# AQM_with_esp32.net
KiCad netlist of a schematic drawn in Altium Designer
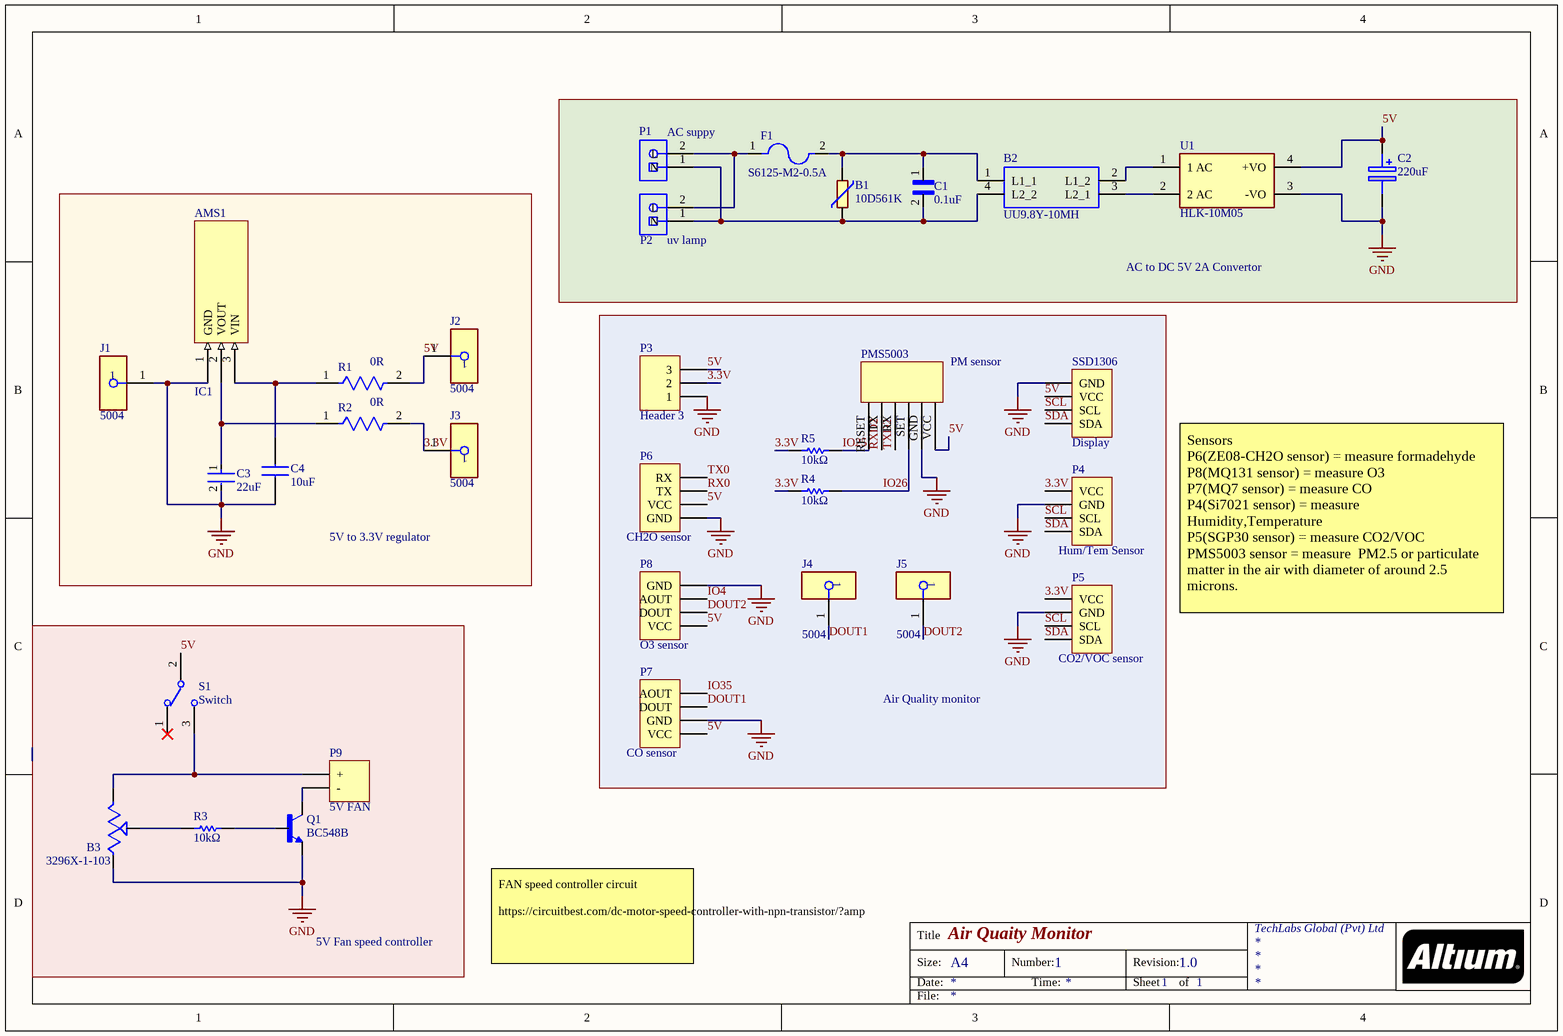
[diagram p0: AQM with esp32.SchDoc]

(export (version "E")
  (design (tool "Eeschema 10.0.6"))
  (components
    (comp (ref "AMS1")
      (value "IC1")
      (footprint "SOT89-150P350X150-3N")
      (fields
        (field (name "MANUFACTURER") "YONGYUTAI")
        (field (name "MFR. PART #") "AMS1117-3.3")
        (field (name "LCSC PART #") "C2904742")
      )
      (libsource (lib "AMS1117-3.3") (part "IC?"))
    )
    (comp (ref "B1")
      (value "10D561K")
      (footprint "10D561K")
      (description "920V 42.3J 180pF@1kHz 460V 350V 504V~616V 2.5kA Plugin Varistors ROHS")
      (fields (field (name "LCSC PART #") "C113236") (field (name "MANUFACTURER") "Hongzhi Elec"))
      (libsource (lib "10D561K") (part "10D561K"))
    )
    (comp (ref "B2")
      (value "UU9.8Y-10MH")
      (footprint "UU98Y10MH")
      (description "10mH@1kHz 1.2Ω 2 500mA 50V Plugin Common Mode Filters ROHS")
      (fields
        (field (name "MANUFACTURER") "FH (Guangdong Fenghua Advanced Tech)")
        (field (name "LCSC PART#") "C75192")
      )
      (libsource (lib "UU9.8Y-10MH") (part "UU9.8Y-10MH"))
    )
    (comp (ref "B3")
      (value "3296X-1-103")
      (footprint "3296X1223LF")
      (description "±10% 10kΩ Plugin Variable Resistors/Potentiometers ROHS")
      (fields
        (field (name "LCSC PART #") "C118955")
        (field (name "MANUFACTURER") "BOCHEN(Chengdu Guosheng Tech)")
      )
      (libsource (lib "3296X-1-103") (part "3296X-1-103"))
    )
    (comp (ref "C1")
      (value "0.1uF")
      (footprint "MPX-104K275VAC-C-D2")
      (description "0.1uF ±10% -40℃~+110℃ X2 275VAC Radial Leaded,P=15mm Suppression Capacitors ROHS")
      (fields (field (name "LCSC PART #") "C3249976") (field (name "MANUFACTURER") "CORETONG"))
      (libsource (lib "MPX-104K275VAC-C-D2") (part "MPX-104K275VAC-C-D2"))
    )
    (comp (ref "C2")
      (value "220uF")
      (footprint "CAPAE830X1050N")
      (fields
        (field (name "MANUFACTURER") "Nichicon")
        (field (name "MFR.PART #") "UUR1C221MNL1GS")
        (field (name "LCSC PART#") "C445237")
      )
      (libsource (lib "UUR1C221MNL1GS") (part "UUR1C221MNL1GS"))
    )
    (comp (ref "C3")
      (value "22uF")
      (footprint "FP-GRM219-0_2-0_15-IPC_A")
      (description "Chip Multilayer Ceramic Capacitors for General Purpose, 0805, 22uF, X5R, 15%, 20%, 16V")
      (fields (field (name "MFR. PART #") "GRM219R61C226ME15L") (field (name "LCSC PART #") "C162295"))
      (libsource (lib "Altium Content Vault") (part "b4654b650e69147ec39a6b967a45e02"))
    )
    (comp (ref "C4")
      (value "10uF")
      (footprint "CAPC1005X70N")
      (description "6.3V 10uF X5R ±20% 0402 Multilayer Ceramic Capacitors MLCC - SMD/SMT ROHS")
      (fields
        (field (name "MANUFACTURER") "Samsung Electro-Mechanics")
        (field (name "MFR. PART #") "CL05A106MQ5NUNC")
      )
      (libsource (lib "CL05A106MQ5NUNC") (part "CL05A106MQ5NUNC"))
    )
    (comp (ref "F1")
      (value "S6125-M2-0.5A")
      (footprint "CAPC6125X25N")
      (description "SMD Fuses ROHS")
      (fields (field (name "LCSC PART #") "C845172") (field (name "MANUFACTURER") "SART(Nanjing Sart Tech)"))
      (libsource (lib "S6125-M2-0.5A") (part "S6125-M2-0.5A"))
    )
    (comp (ref "J1")
      (value "5004")
      (footprint "FP-5004-MFG")
      (description "PC TEST POINT MINIATURE YELLOW")
      (fields (field (name "MANUFACTURER") "Keystone") (field (name "LCSC PART #") "C2906762"))
      (libsource (lib "") (part "98815daf2f2c152b0c43f5ab9800df6_2"))
    )
    (comp (ref "J2")
      (value "5004")
      (footprint "FP-5004-MFG")
      (description "PC TEST POINT MINIATURE YELLOW")
      (fields (field (name "MANUFACTURER") "Keystone") (field (name "LCSC PART #") "C2906762"))
      (libsource (lib "Altium Content Vault") (part "98815daf2f2c152b0c43f5ab9800df6"))
    )
    (comp (ref "J3")
      (value "5004")
      (footprint "FP-5004-MFG")
      (description "PC TEST POINT MINIATURE YELLOW")
      (fields (field (name "MANUFACTURER") "Keystone") (field (name "LCSC PART #") "C2906762"))
      (libsource (lib "Altium Content Vault") (part "98815daf2f2c152b0c43f5ab9800df6"))
    )
    (comp (ref "J4")
      (value "5004")
      (footprint "FP-5004-MFG")
      (description "PC TEST POINT MINIATURE YELLOW")
      (fields (field (name "MANUFACTURER") "Keystone") (field (name "LCSC PART #") "C2906762"))
      (libsource (lib "") (part "98815daf2f2c152b0c43f5ab9800df6_1"))
    )
    (comp (ref "J5")
      (value "5004")
      (footprint "FP-5004-MFG")
      (description "PC TEST POINT MINIATURE YELLOW")
      (fields (field (name "MANUFACTURER") "Keystone") (field (name "LCSC PART #") "C2906762"))
      (libsource (lib "") (part "98815daf2f2c152b0c43f5ab9800df6_1"))
    )
    (comp (ref "P1")
      (value "AC suppy")
      (footprint "PHOE-1729128-2_V")
      (description "13.5A 400V Green Straight pin 5.08mm 1 2 Plugin,P=5.08mm Screw terminal ROHS")
      (fields (field (name "MFR.PART #") "1729128") (field (name "LCSC PART#") "C91153"))
      (libsource (lib "Altium Content Vault") (part "CN-2P-F-R2"))
    )
    (comp (ref "P2")
      (value "uv lamp")
      (footprint "PHOE-1729128-2_V")
      (description "13.5A 400V Green Straight pin 5.08mm 1 2 Plugin,P=5.08mm Screw terminal ROHS")
      (fields (field (name "MFR.PART #") "1729128") (field (name "LCSC PART#") "C91153"))
      (libsource (lib "Altium Content Vault") (part "CN-2P-F-R2"))
    )
    (comp (ref "P3")
      (value "Header 3")
      (footprint "HDR1X3")
      (description "Header, 3-Pin")
      (fields (field (name "PUBLISHER") "Altium Limited"))
      (libsource (lib "Miscellaneous Connectors") (part "Header 3"))
    )
    (comp (ref "P4")
      (value "Hum/Tem Sensor")
      (footprint "HDR1X4")
      (description "Si7021 Header, 4-Pin")
      (libsource (lib "") (part "Header 4_2"))
    )
    (comp (ref "P5")
      (value "CO2/VOC sensor")
      (footprint "HDR1X4")
      (description "SGP30 Header, 4-Pin")
      (fields (field (name "PUBLISHER") "Altium Limited"))
      (libsource (lib "") (part "Header 4_2"))
    )
    (comp (ref "P6")
      (value "CH2O sensor")
      (footprint "HDR1X4")
      (description "- Sensor Modules ROHS")
      (fields
        (field (name "MFR.PART #") "ZE08-CH2O")
        (field (name "MANUFACTURER") "Zhengzhou Winsen Elec Tech")
      )
      (libsource (lib "") (part "Header 4_3"))
    )
    (comp (ref "P7")
      (value "CO sensor")
      (footprint "HDR1X4")
      (description "MQ7 Header, 4-Pin")
      (fields (field (name "PUBLISHER") "Altium Limited"))
      (libsource (lib "Miscellaneous Connectors") (part "Header 4"))
    )
    (comp (ref "P8")
      (value "O3 sensor")
      (footprint "HDR1X4")
      (description "MQ131 Header, 4-Pin")
      (fields (field (name "PUBLISHER") "Altium Limited"))
      (libsource (lib "") (part "Header 4_1"))
    )
    (comp (ref "P9")
      (value "5V FAN")
      (footprint "HDR1X2")
      (description "Header, 2-Pin")
      (fields (field (name "PUBLISHER") "Altium Limited"))
      (libsource (lib "Miscellaneous Connectors") (part "Header 2"))
    )
    (comp (ref "PMS5003")
      (value "PM sensor")
      (footprint "PMS5003 PM2.5 Sensor")
      (description "PMS5003 Sensor Modules ROHS")
      (fields (field (name "MFR.PART #") "PMS5003") (field (name "MANUFACTURER") "Beijing Plantower"))
      (libsource (lib "DIY Air Quality Monitor Library") (part "PMS5003 PM2.5 Sensor"))
    )
    (comp (ref "Q1")
      (value "BC548B")
      (footprint "BC548B")
      (fields (field (name "MANUFACTURER") "LGE") (field (name "LCSC PART#") "C713615"))
      (libsource (lib "BC548B") (part "BC548B"))
    )
    (comp (ref "R1")
      (value "0R")
      (footprint "FP-RC0402-0_4-IPC_A")
      (description "RES SMD 0 OHM JUMPER 1/16W 0402")
      (fields (field (name "MANUFACTURER") "Yageo") (field (name "LCSC PART #") "C106231"))
      (libsource (lib "Altium Content Vault") (part "1029c3af85768c4190bb7ad29bc67b5"))
    )
    (comp (ref "R2")
      (value "0R")
      (footprint "FP-RC0402-0_4-IPC_A")
      (description "RES SMD 0 OHM JUMPER 1/16W 0402")
      (fields (field (name "MANUFACTURER") "Yageo") (field (name "LCSC PART #") "C106231"))
      (libsource (lib "Altium Content Vault") (part "1029c3af85768c4190bb7ad29bc67b5"))
    )
    (comp (ref "R3")
      (value "10kΩ")
      (footprint "RESC1005X40X25LL05T10")
      (description "62.5mW 50V ±100ppm/℃ ±1% -55℃~+155℃ 10kΩ 0402 Chip Resistor - Surface Mount ROHS")
      (fields (field (name "MFR. PART #") "RC0402FR-0710KL") (field (name "MANUFACTURER") "Yageo / Phycomp"))
      (libsource (lib "Altium Content Vault") (part "RES"))
    )
    (comp (ref "R4")
      (value "10kΩ")
      (footprint "RESC1005X40X25LL05T10")
      (description "62.5mW 50V ±100ppm/℃ ±1% -55℃~+155℃ 10kΩ 0402 Chip Resistor - Surface Mount ROHS")
      (fields (field (name "MFR. PART #") "RC0402FR-0710KL") (field (name "MANUFACTURER") "Yageo / Phycomp"))
      (libsource (lib "Altium Content Vault") (part "RES"))
    )
    (comp (ref "R5")
      (value "10kΩ")
      (footprint "RESC1005X40X25LL05T10")
      (description "62.5mW 50V ±100ppm/℃ ±1% -55℃~+155℃ 10kΩ 0402 Chip Resistor - Surface Mount ROHS")
      (fields (field (name "MFR. PART #") "RC0402FR-0710KL") (field (name "MANUFACTURER") "Yageo / Phycomp"))
      (libsource (lib "Altium Content Vault") (part "RES"))
    )
    (comp (ref "S1")
      (value "Switch")
      (footprint "SK3245SL1A")
      (fields
        (field (name "MANUFACTURER") "XKB Connectivity")
        (field (name "MFR. PART #") "SK-3245S-L1-A")
        (field (name "LCSC PART #") "C405951")
      )
      (libsource (lib "SK-3245S-L1-A") (part "SK-3245S-L1-A"))
    )
    (comp (ref "SSD1306")
      (value "Display")
      (footprint "HDR1X4")
      (description "Header, 4-Pin")
      (fields (field (name "PUBLISHER") "Altium Limited"))
      (libsource (lib "") (part "Header 4_4"))
    )
    (comp (ref "U1")
      (value "HLK-10M05")
      (footprint "FP-HLK-10M05-MFG")
      (description "5V 2A 90VAC~265VAC 1 120V~350V Isolated Regulated 10W AC-DC 80% Plugin Power Modules ROHS")
      (fields (field (name "MANUFACTURER") "HI-LINK") (field (name "LCSC PART#") "C403745"))
      (libsource (lib "Altium Content Vault") (part "a65b17ccb3a75dffb3c3e849074403b"))
    )
  )
  (nets
    (net (code "1") (name "/3.3V") (class "Default")
      (node (ref "J3") (pin "1") (pinfunction "1_1") (pintype "passive"))
      (node (ref "P3") (pin "2") (pinfunction "2_2") (pintype "passive"))
      (node (ref "P4") (pin "1") (pinfunction "VCC_1") (pintype "passive"))
      (node (ref "P5") (pin "1") (pinfunction "VCC_1") (pintype "passive"))
      (node (ref "R2") (pin "2") (pinfunction "2_2") (pintype "passive"))
      (node (ref "R4") (pin "1") (pinfunction "1_1") (pintype "passive"))
      (node (ref "R5") (pin "1") (pinfunction "1_1") (pintype "passive"))
    )
    (net (code "2") (name "/5V") (class "Default")
      (node (ref "C2") (pin "1") (pinfunction "+_1") (pintype "passive"))
      (node (ref "J2") (pin "1") (pinfunction "1_1") (pintype "passive"))
      (node (ref "P3") (pin "3") (pinfunction "3_3") (pintype "passive"))
      (node (ref "P6") (pin "2") (pinfunction "VCC_2") (pintype "passive"))
      (node (ref "P7") (pin "1") (pinfunction "VCC_1") (pintype "passive"))
      (node (ref "P8") (pin "1") (pinfunction "VCC_1") (pintype "passive"))
      (node (ref "PMS5003") (pin "VCC") (pintype "passive"))
      (node (ref "R1") (pin "2") (pinfunction "2_2") (pintype "passive"))
      (node (ref "S1") (pin "2") (pinfunction "2_2") (pintype "passive"))
      (node (ref "SSD1306") (pin "2") (pinfunction "VCC_2") (pintype "passive"))
      (node (ref "U1") (pin "4") (pinfunction "+VO_4") (pintype "power_in"))
    )
    (net (code "3") (name "/DOUT1") (class "Default")
      (node (ref "J4") (pin "1") (pinfunction "1_1") (pintype "passive"))
      (node (ref "P7") (pin "3") (pinfunction "DOUT_3") (pintype "passive"))
    )
    (net (code "4") (name "/DOUT2") (class "Default")
      (node (ref "J5") (pin "1") (pinfunction "1_1") (pintype "passive"))
      (node (ref "P8") (pin "2") (pinfunction "DOUT_2") (pintype "passive"))
    )
    (net (code "5") (name "/IO4") (class "Default")
      (node (ref "P8") (pin "3") (pinfunction "AOUT_3") (pintype "passive"))
    )
    (net (code "6") (name "/IO25") (class "Default")
      (node (ref "PMS5003") (pin "RESET") (pintype "passive"))
      (node (ref "R5") (pin "2") (pinfunction "2_2") (pintype "passive"))
    )
    (net (code "7") (name "/IO26") (class "Default")
      (node (ref "PMS5003") (pin "SET") (pintype "passive"))
      (node (ref "R4") (pin "2") (pinfunction "2_2") (pintype "passive"))
    )
    (net (code "8") (name "/IO35") (class "Default")
      (node (ref "P7") (pin "4") (pinfunction "AOUT_4") (pintype "passive"))
    )
    (net (code "9") (name "/RX0") (class "Default")
      (node (ref "P6") (pin "3") (pinfunction "TX_3") (pintype "passive"))
    )
    (net (code "10") (name "/RXD2") (class "Default") (node (ref "PMS5003") (pin "TX") (pintype "passive")))
    (net (code "11") (name "/SCL") (class "Default")
      (node (ref "P4") (pin "3") (pinfunction "SCL_3") (pintype "passive"))
      (node (ref "P5") (pin "3") (pinfunction "SCL_3") (pintype "passive"))
      (node (ref "SSD1306") (pin "3") (pinfunction "SCL_3") (pintype "passive"))
    )
    (net (code "12") (name "/SDA") (class "Default")
      (node (ref "P4") (pin "4") (pinfunction "SDA_4") (pintype "passive"))
      (node (ref "P5") (pin "4") (pinfunction "SDA_4") (pintype "passive"))
      (node (ref "SSD1306") (pin "4") (pinfunction "SDA_4") (pintype "passive"))
    )
    (net (code "13") (name "/TX0") (class "Default")
      (node (ref "P6") (pin "4") (pinfunction "RX_4") (pintype "passive"))
    )
    (net (code "14") (name "/TXD2") (class "Default") (node (ref "PMS5003") (pin "RX") (pintype "passive")))
    (net (code "15") (name "GND") (class "Default")
      (node (ref "AMS1") (pin "1") (pinfunction "GND_1") (pintype "input"))
      (node (ref "B3") (pin "1") (pinfunction "A_1") (pintype "passive"))
      (node (ref "C2") (pin "2") (pinfunction "-_2") (pintype "passive"))
      (node (ref "C3") (pin "2") (pinfunction "2_2") (pintype "passive"))
      (node (ref "C4") (pin "1") (pinfunction "1_1") (pintype "passive"))
      (node (ref "J1") (pin "1") (pinfunction "1_1") (pintype "passive"))
      (node (ref "P3") (pin "1") (pinfunction "1_1") (pintype "passive"))
      (node (ref "P4") (pin "2") (pinfunction "GND_2") (pintype "passive"))
      (node (ref "P5") (pin "2") (pinfunction "GND_2") (pintype "passive"))
      (node (ref "P6") (pin "1") (pinfunction "GND_1") (pintype "passive"))
      (node (ref "P7") (pin "2") (pinfunction "GND_2") (pintype "passive"))
      (node (ref "P8") (pin "4") (pinfunction "GND_4") (pintype "passive"))
      (node (ref "PMS5003") (pin "GND") (pintype "passive"))
      (node (ref "Q1") (pin "3") (pinfunction "E_3") (pintype "passive"))
      (node (ref "SSD1306") (pin "1") (pinfunction "GND_1") (pintype "passive"))
      (node (ref "U1") (pin "3") (pinfunction "-VO_3") (pintype "power_in"))
    )
    (net (code "16") (name "Net-(AMS1-VIN)") (class "Default")
      (node (ref "AMS1") (pin "3") (pinfunction "VIN_3") (pintype "input"))
      (node (ref "C4") (pin "2") (pinfunction "2_2") (pintype "passive"))
      (node (ref "R1") (pin "1") (pinfunction "1_1") (pintype "passive"))
    )
    (net (code "17") (name "Net-(AMS1-VOUT)") (class "Default")
      (node (ref "AMS1") (pin "2") (pinfunction "VOUT_2") (pintype "input"))
      (node (ref "C3") (pin "1") (pinfunction "1_1") (pintype "passive"))
      (node (ref "R2") (pin "1") (pinfunction "1_1") (pintype "passive"))
    )
    (net (code "18") (name "Net-(B2-L1_1)") (class "Default")
      (node (ref "B1") (pin "1") (pinfunction "1_1") (pintype "passive"))
      (node (ref "B2") (pin "1") (pinfunction "L1_1_1") (pintype "passive"))
      (node (ref "C1") (pin "1") (pinfunction "1_1") (pintype "passive"))
      (node (ref "F1") (pin "2") (pinfunction "2_2") (pintype "passive"))
    )
    (net (code "19") (name "Net-(B2-L1_2)") (class "Default")
      (node (ref "B2") (pin "2") (pinfunction "L1_2_2") (pintype "passive"))
      (node (ref "U1") (pin "1") (pinfunction "1_AC_1") (pintype "passive"))
    )
    (net (code "20") (name "Net-(B2-L2_1)") (class "Default")
      (node (ref "B2") (pin "3") (pinfunction "L2_1_3") (pintype "passive"))
      (node (ref "U1") (pin "2") (pinfunction "2_AC_2") (pintype "passive"))
    )
    (net (code "21") (name "Net-(B2-L2_2)") (class "Default")
      (node (ref "B1") (pin "2") (pinfunction "2_2") (pintype "passive"))
      (node (ref "B2") (pin "4") (pinfunction "L2_2_4") (pintype "passive"))
      (node (ref "C1") (pin "2") (pinfunction "2_2") (pintype "passive"))
      (node (ref "P1") (pin "1") (pinfunction "N_1") (pintype "passive"))
      (node (ref "P2") (pin "1") (pinfunction "N_1") (pintype "passive"))
    )
    (net (code "22") (name "Net-(B3-B)") (class "Default")
      (node (ref "B3") (pin "2") (pinfunction "B_2") (pintype "passive"))
      (node (ref "R3") (pin "1") (pinfunction "1_1") (pintype "passive"))
    )
    (net (code "23") (name "Net-(B3-C)") (class "Default")
      (node (ref "B3") (pin "3") (pinfunction "C_3") (pintype "passive"))
      (node (ref "P9") (pin "1") (pinfunction "+_1") (pintype "passive"))
      (node (ref "S1") (pin "3") (pinfunction "3_3") (pintype "passive"))
    )
    (net (code "24") (name "Net-(P1-L)") (class "Default")
      (node (ref "F1") (pin "1") (pinfunction "1_1") (pintype "passive"))
      (node (ref "P1") (pin "2") (pinfunction "L_2") (pintype "passive"))
      (node (ref "P2") (pin "2") (pinfunction "L_2") (pintype "passive"))
    )
    (net (code "25") (name "Net-(P9--)") (class "Default")
      (node (ref "P9") (pin "2") (pinfunction "-_2") (pintype "passive"))
      (node (ref "Q1") (pin "1") (pinfunction "C_1") (pintype "passive"))
    )
    (net (code "26") (name "Net-(Q1-B)") (class "Default")
      (node (ref "Q1") (pin "2") (pinfunction "B_2") (pintype "passive"))
      (node (ref "R3") (pin "2") (pinfunction "2_2") (pintype "passive"))
    )
    (net (code "27") (name "unconnected-(S1-Pad1)") (class "Default")
      (node (ref "S1") (pin "1") (pinfunction "1_1") (pintype "passive+no_connect"))
    )
  )
)
